# Esquematico_Deck_-_Crazyflie_V2.net
KiCad netlist of a schematic drawn in Altium Designer
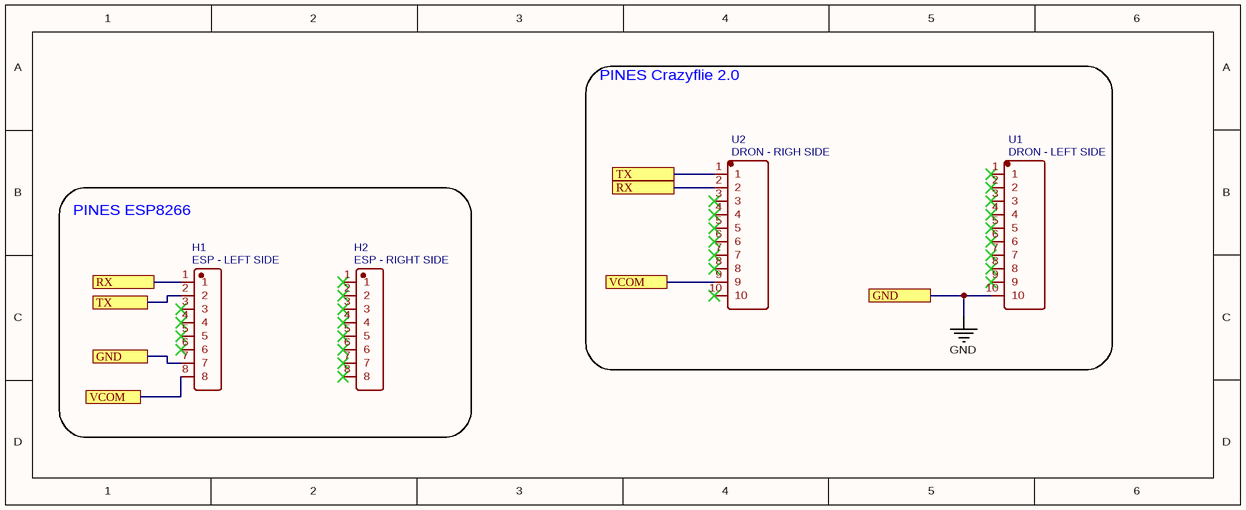
[diagram p0: Esquematico Deck - Crazyflie V2.schdoc]

(export (version "E")
  (design (tool "Eeschema 10.0.6"))
  (components
    (comp (ref "H1")
      (value "ESP - LEFT SIDE")
      (footprint "HDR1X8")
      (fields
        (field (name "BOM_SUPPLIER PART") "C2935914")
        (field (name "BOM_MANUFACTURER PART") "DZ254R-11-08-63")
        (field (name "CONTRIBUTOR") "LCSC")
      )
      (libsource (lib "altium-import") (part "root_0_ESP - LEFT SIDE_"))
    )
    (comp (ref "H2")
      (value "ESP - RIGHT SIDE")
      (footprint "HDR1X8")
      (fields
        (field (name "BOM_SUPPLIER PART") "C2935914")
        (field (name "BOM_MANUFACTURER PART") "DZ254R-11-08-63")
        (field (name "CONTRIBUTOR") "LCSC")
      )
      (libsource (lib "altium-import") (part "root_0_ESP - RIGHT SIDE_"))
    )
    (comp (ref "U1")
      (value "DRON - LEFT SIDE")
      (footprint "HDR1X10")
      (fields
        (field (name "BOM_SUPPLIER PART") "C350282")
        (field (name "BOM_MANUFACTURER PART") "2543U-110CNG1SNT01")
        (field (name "CONTRIBUTOR") "LCSC")
      )
      (libsource (lib "altium-import") (part "root_0_DRON - LEFT SIDE_"))
    )
    (comp (ref "U2")
      (value "DRON - RIGH SIDE")
      (footprint "HDR1X10")
      (fields
        (field (name "BOM_SUPPLIER PART") "C350282")
        (field (name "BOM_MANUFACTURER PART") "2543U-110CNG1SNT01")
        (field (name "CONTRIBUTOR") "LCSC")
      )
      (libsource (lib "altium-import") (part "root_0_DRON - RIGH SIDE_"))
    )
  )
  (nets
    (net (code "1") (name "/RX") (class "Default")
      (node (ref "H1") (pin "1") (pinfunction "1_1") (pintype "passive"))
      (node (ref "U2") (pin "2") (pinfunction "2_2") (pintype "passive"))
    )
    (net (code "2") (name "/TX") (class "Default")
      (node (ref "H1") (pin "2") (pinfunction "2_2") (pintype "passive"))
      (node (ref "U2") (pin "1") (pinfunction "1_1") (pintype "passive"))
    )
    (net (code "3") (name "/VCOM") (class "Default")
      (node (ref "H1") (pin "8") (pinfunction "8_8") (pintype "passive"))
      (node (ref "U2") (pin "9") (pinfunction "9_9") (pintype "passive"))
    )
    (net (code "4") (name "GND") (class "Default")
      (node (ref "H1") (pin "7") (pinfunction "7_7") (pintype "passive"))
      (node (ref "U1") (pin "10") (pinfunction "10_10") (pintype "passive"))
    )
    (net (code "5") (name "unconnected-(H1-Pad3)") (class "Default")
      (node (ref "H1") (pin "3") (pinfunction "3_3") (pintype "passive+no_connect"))
    )
    (net (code "6") (name "unconnected-(H1-Pad4)") (class "Default")
      (node (ref "H1") (pin "4") (pinfunction "4_4") (pintype "passive+no_connect"))
    )
    (net (code "7") (name "unconnected-(H1-Pad5)") (class "Default")
      (node (ref "H1") (pin "5") (pinfunction "5_5") (pintype "passive+no_connect"))
    )
    (net (code "8") (name "unconnected-(H1-Pad6)") (class "Default")
      (node (ref "H1") (pin "6") (pinfunction "6_6") (pintype "passive+no_connect"))
    )
    (net (code "9") (name "unconnected-(H2-Pad1)") (class "Default")
      (node (ref "H2") (pin "1") (pinfunction "1_1") (pintype "passive+no_connect"))
    )
    (net (code "10") (name "unconnected-(H2-Pad2)") (class "Default")
      (node (ref "H2") (pin "2") (pinfunction "2_2") (pintype "passive+no_connect"))
    )
    (net (code "11") (name "unconnected-(H2-Pad3)") (class "Default")
      (node (ref "H2") (pin "3") (pinfunction "3_3") (pintype "passive+no_connect"))
    )
    (net (code "12") (name "unconnected-(H2-Pad4)") (class "Default")
      (node (ref "H2") (pin "4") (pinfunction "4_4") (pintype "passive+no_connect"))
    )
    (net (code "13") (name "unconnected-(H2-Pad5)") (class "Default")
      (node (ref "H2") (pin "5") (pinfunction "5_5") (pintype "passive+no_connect"))
    )
    (net (code "14") (name "unconnected-(H2-Pad6)") (class "Default")
      (node (ref "H2") (pin "6") (pinfunction "6_6") (pintype "passive+no_connect"))
    )
    (net (code "15") (name "unconnected-(H2-Pad7)") (class "Default")
      (node (ref "H2") (pin "7") (pinfunction "7_7") (pintype "passive+no_connect"))
    )
    (net (code "16") (name "unconnected-(H2-Pad8)") (class "Default")
      (node (ref "H2") (pin "8") (pinfunction "8_8") (pintype "passive+no_connect"))
    )
    (net (code "17") (name "unconnected-(U1-Pad1)") (class "Default")
      (node (ref "U1") (pin "1") (pinfunction "1_1") (pintype "passive+no_connect"))
    )
    (net (code "18") (name "unconnected-(U1-Pad2)") (class "Default")
      (node (ref "U1") (pin "2") (pinfunction "2_2") (pintype "passive+no_connect"))
    )
    (net (code "19") (name "unconnected-(U1-Pad3)") (class "Default")
      (node (ref "U1") (pin "3") (pinfunction "3_3") (pintype "passive+no_connect"))
    )
    (net (code "20") (name "unconnected-(U1-Pad4)") (class "Default")
      (node (ref "U1") (pin "4") (pinfunction "4_4") (pintype "passive+no_connect"))
    )
    (net (code "21") (name "unconnected-(U1-Pad5)") (class "Default")
      (node (ref "U1") (pin "5") (pinfunction "5_5") (pintype "passive+no_connect"))
    )
    (net (code "22") (name "unconnected-(U1-Pad6)") (class "Default")
      (node (ref "U1") (pin "6") (pinfunction "6_6") (pintype "passive+no_connect"))
    )
    (net (code "23") (name "unconnected-(U1-Pad7)") (class "Default")
      (node (ref "U1") (pin "7") (pinfunction "7_7") (pintype "passive+no_connect"))
    )
    (net (code "24") (name "unconnected-(U1-Pad8)") (class "Default")
      (node (ref "U1") (pin "8") (pinfunction "8_8") (pintype "passive+no_connect"))
    )
    (net (code "25") (name "unconnected-(U1-Pad9)") (class "Default")
      (node (ref "U1") (pin "9") (pinfunction "9_9") (pintype "passive+no_connect"))
    )
    (net (code "26") (name "unconnected-(U2-Pad3)") (class "Default")
      (node (ref "U2") (pin "3") (pinfunction "3_3") (pintype "passive+no_connect"))
    )
    (net (code "27") (name "unconnected-(U2-Pad4)") (class "Default")
      (node (ref "U2") (pin "4") (pinfunction "4_4") (pintype "passive+no_connect"))
    )
    (net (code "28") (name "unconnected-(U2-Pad5)") (class "Default")
      (node (ref "U2") (pin "5") (pinfunction "5_5") (pintype "passive+no_connect"))
    )
    (net (code "29") (name "unconnected-(U2-Pad6)") (class "Default")
      (node (ref "U2") (pin "6") (pinfunction "6_6") (pintype "passive+no_connect"))
    )
    (net (code "30") (name "unconnected-(U2-Pad7)") (class "Default")
      (node (ref "U2") (pin "7") (pinfunction "7_7") (pintype "passive+no_connect"))
    )
    (net (code "31") (name "unconnected-(U2-Pad8)") (class "Default")
      (node (ref "U2") (pin "8") (pinfunction "8_8") (pintype "passive+no_connect"))
    )
    (net (code "32") (name "unconnected-(U2-Pad10)") (class "Default")
      (node (ref "U2") (pin "10") (pinfunction "10_10") (pintype "passive+no_connect"))
    )
  )
)
